# breadboard-small.net
KiCad netlist of a schematic drawn in EAGLE
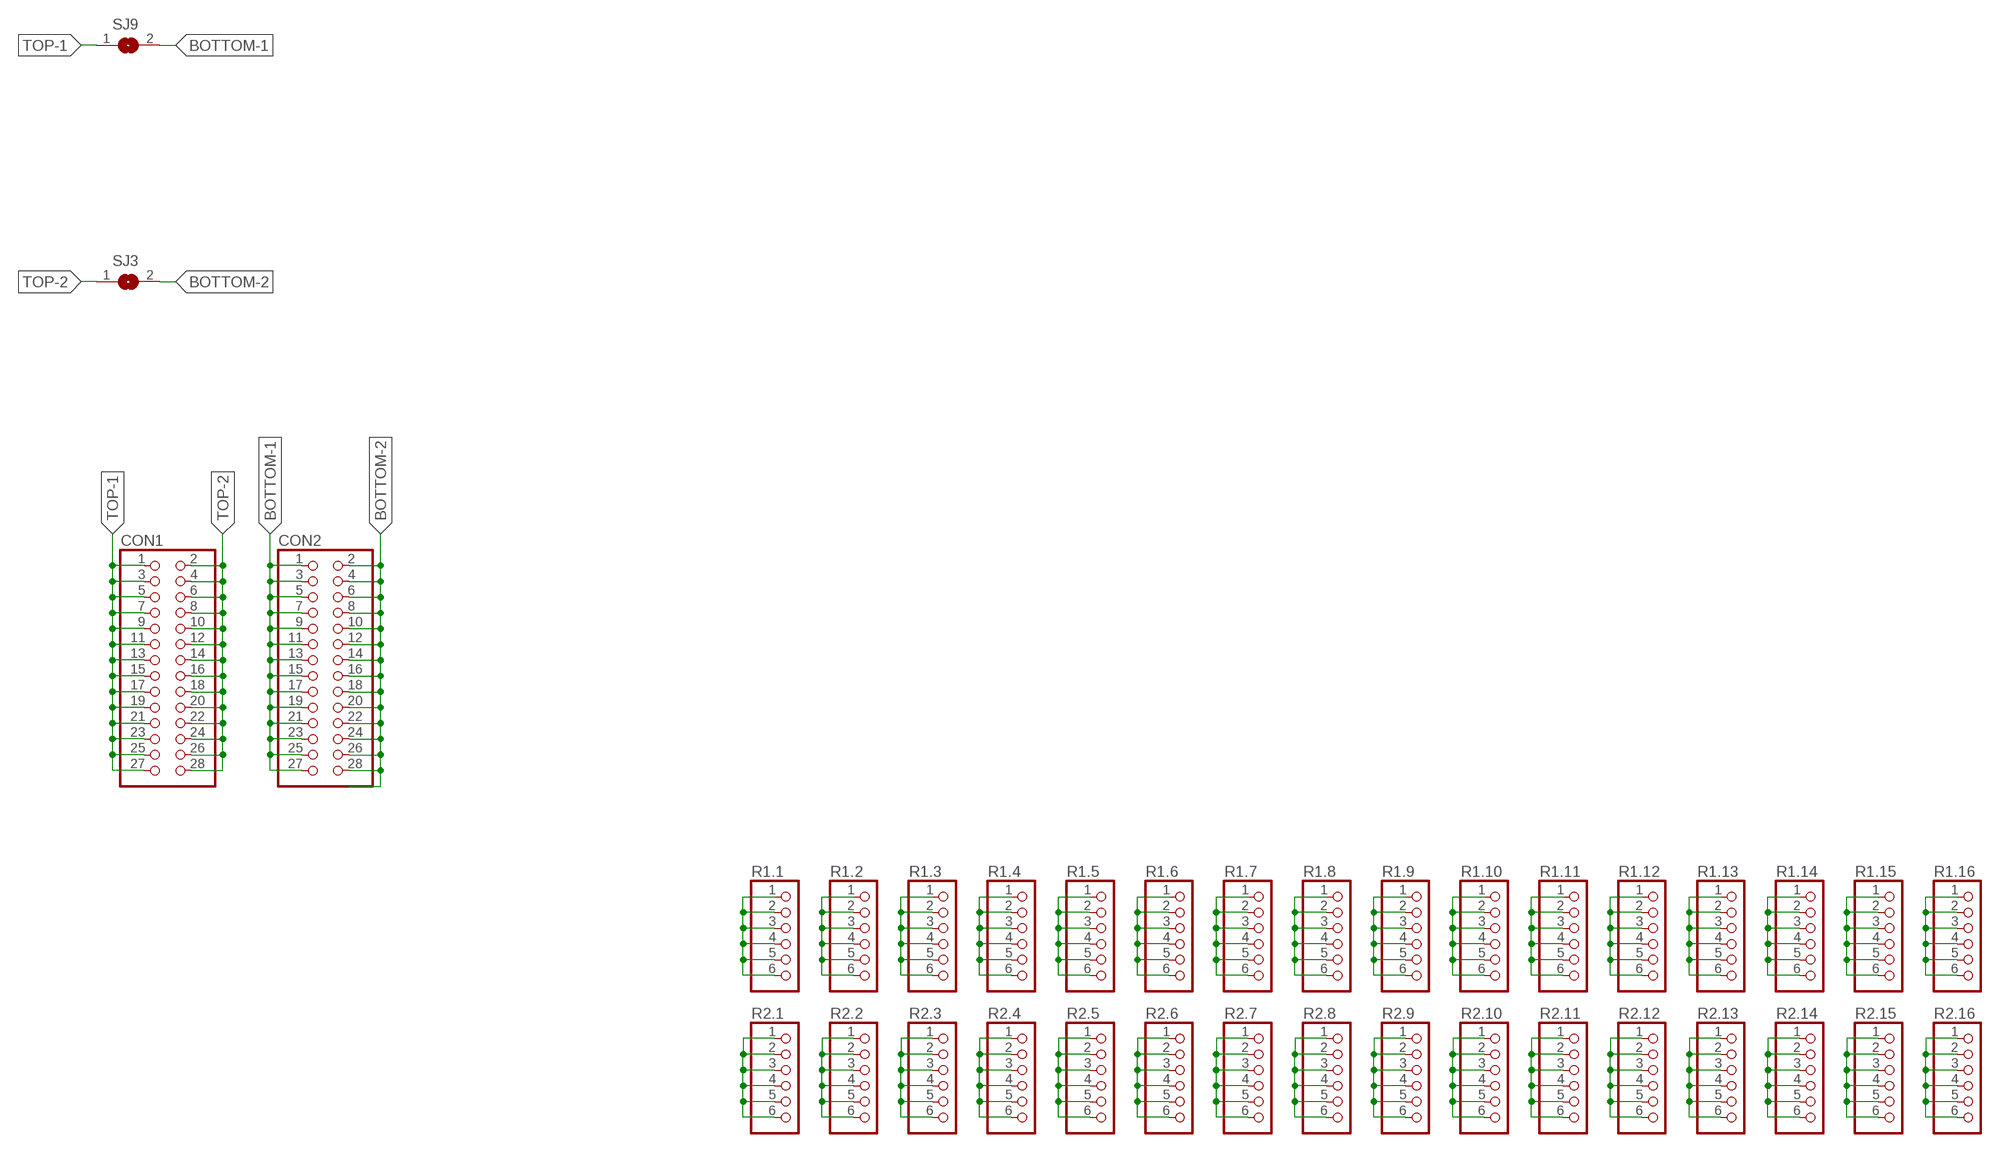
[diagram p0: schematic, sheet 1]

(export (version "E")
  (design (tool "Eeschema 10.0.6"))
  (components
    (comp (ref "CON1")
      (value "GENERIC-2X14")
      (footprint "eagle-import:PINHEADER-100MIL-2X14-NOSILK")
      (libsource (lib "eagle-import") (part "GENERIC-2X14"))
    )
    (comp (ref "CON2")
      (value "GENERIC-2X14")
      (footprint "eagle-import:PINHEADER-100MIL-2X14-NOSILK")
      (libsource (lib "eagle-import") (part "GENERIC-2X14"))
    )
    (comp (ref "R1.1")
      (value "GENERIC-1X6")
      (footprint "eagle-import:PINHEADER-100MIL-1X6-NOSILK")
      (libsource (lib "eagle-import") (part "GENERIC-1X6"))
    )
    (comp (ref "R1.2")
      (value "GENERIC-1X6")
      (footprint "eagle-import:PINHEADER-100MIL-1X6-NOSILK")
      (libsource (lib "eagle-import") (part "GENERIC-1X6"))
    )
    (comp (ref "R1.3")
      (value "GENERIC-1X6")
      (footprint "eagle-import:PINHEADER-100MIL-1X6-NOSILK")
      (libsource (lib "eagle-import") (part "GENERIC-1X6"))
    )
    (comp (ref "R1.4")
      (value "GENERIC-1X6")
      (footprint "eagle-import:PINHEADER-100MIL-1X6-NOSILK")
      (libsource (lib "eagle-import") (part "GENERIC-1X6"))
    )
    (comp (ref "R1.5")
      (value "GENERIC-1X6")
      (footprint "eagle-import:PINHEADER-100MIL-1X6-NOSILK")
      (libsource (lib "eagle-import") (part "GENERIC-1X6"))
    )
    (comp (ref "R1.6")
      (value "GENERIC-1X6")
      (footprint "eagle-import:PINHEADER-100MIL-1X6-NOSILK")
      (libsource (lib "eagle-import") (part "GENERIC-1X6"))
    )
    (comp (ref "R1.7")
      (value "GENERIC-1X6")
      (footprint "eagle-import:PINHEADER-100MIL-1X6-NOSILK")
      (libsource (lib "eagle-import") (part "GENERIC-1X6"))
    )
    (comp (ref "R1.8")
      (value "GENERIC-1X6")
      (footprint "eagle-import:PINHEADER-100MIL-1X6-NOSILK")
      (libsource (lib "eagle-import") (part "GENERIC-1X6"))
    )
    (comp (ref "R1.9")
      (value "GENERIC-1X6")
      (footprint "eagle-import:PINHEADER-100MIL-1X6-NOSILK")
      (libsource (lib "eagle-import") (part "GENERIC-1X6"))
    )
    (comp (ref "R1.10")
      (value "GENERIC-1X6")
      (footprint "eagle-import:PINHEADER-100MIL-1X6-NOSILK")
      (libsource (lib "eagle-import") (part "GENERIC-1X6"))
    )
    (comp (ref "R1.11")
      (value "GENERIC-1X6")
      (footprint "eagle-import:PINHEADER-100MIL-1X6-NOSILK")
      (libsource (lib "eagle-import") (part "GENERIC-1X6"))
    )
    (comp (ref "R1.12")
      (value "GENERIC-1X6")
      (footprint "eagle-import:PINHEADER-100MIL-1X6-NOSILK")
      (libsource (lib "eagle-import") (part "GENERIC-1X6"))
    )
    (comp (ref "R1.13")
      (value "GENERIC-1X6")
      (footprint "eagle-import:PINHEADER-100MIL-1X6-NOSILK")
      (libsource (lib "eagle-import") (part "GENERIC-1X6"))
    )
    (comp (ref "R1.14")
      (value "GENERIC-1X6")
      (footprint "eagle-import:PINHEADER-100MIL-1X6-NOSILK")
      (libsource (lib "eagle-import") (part "GENERIC-1X6"))
    )
    (comp (ref "R1.15")
      (value "GENERIC-1X6")
      (footprint "eagle-import:PINHEADER-100MIL-1X6-NOSILK")
      (libsource (lib "eagle-import") (part "GENERIC-1X6"))
    )
    (comp (ref "R1.16")
      (value "GENERIC-1X6")
      (footprint "eagle-import:PINHEADER-100MIL-1X6-NOSILK")
      (libsource (lib "eagle-import") (part "GENERIC-1X6"))
    )
    (comp (ref "R2.1")
      (value "GENERIC-1X6")
      (footprint "eagle-import:PINHEADER-100MIL-1X6-NOSILK")
      (libsource (lib "eagle-import") (part "GENERIC-1X6"))
    )
    (comp (ref "R2.2")
      (value "GENERIC-1X6")
      (footprint "eagle-import:PINHEADER-100MIL-1X6-NOSILK")
      (libsource (lib "eagle-import") (part "GENERIC-1X6"))
    )
    (comp (ref "R2.3")
      (value "GENERIC-1X6")
      (footprint "eagle-import:PINHEADER-100MIL-1X6-NOSILK")
      (libsource (lib "eagle-import") (part "GENERIC-1X6"))
    )
    (comp (ref "R2.4")
      (value "GENERIC-1X6")
      (footprint "eagle-import:PINHEADER-100MIL-1X6-NOSILK")
      (libsource (lib "eagle-import") (part "GENERIC-1X6"))
    )
    (comp (ref "R2.5")
      (value "GENERIC-1X6")
      (footprint "eagle-import:PINHEADER-100MIL-1X6-NOSILK")
      (libsource (lib "eagle-import") (part "GENERIC-1X6"))
    )
    (comp (ref "R2.6")
      (value "GENERIC-1X6")
      (footprint "eagle-import:PINHEADER-100MIL-1X6-NOSILK")
      (libsource (lib "eagle-import") (part "GENERIC-1X6"))
    )
    (comp (ref "R2.7")
      (value "GENERIC-1X6")
      (footprint "eagle-import:PINHEADER-100MIL-1X6-NOSILK")
      (libsource (lib "eagle-import") (part "GENERIC-1X6"))
    )
    (comp (ref "R2.8")
      (value "GENERIC-1X6")
      (footprint "eagle-import:PINHEADER-100MIL-1X6-NOSILK")
      (libsource (lib "eagle-import") (part "GENERIC-1X6"))
    )
    (comp (ref "R2.9")
      (value "GENERIC-1X6")
      (footprint "eagle-import:PINHEADER-100MIL-1X6-NOSILK")
      (libsource (lib "eagle-import") (part "GENERIC-1X6"))
    )
    (comp (ref "R2.10")
      (value "GENERIC-1X6")
      (footprint "eagle-import:PINHEADER-100MIL-1X6-NOSILK")
      (libsource (lib "eagle-import") (part "GENERIC-1X6"))
    )
    (comp (ref "R2.11")
      (value "GENERIC-1X6")
      (footprint "eagle-import:PINHEADER-100MIL-1X6-NOSILK")
      (libsource (lib "eagle-import") (part "GENERIC-1X6"))
    )
    (comp (ref "R2.12")
      (value "GENERIC-1X6")
      (footprint "eagle-import:PINHEADER-100MIL-1X6-NOSILK")
      (libsource (lib "eagle-import") (part "GENERIC-1X6"))
    )
    (comp (ref "R2.13")
      (value "GENERIC-1X6")
      (footprint "eagle-import:PINHEADER-100MIL-1X6-NOSILK")
      (libsource (lib "eagle-import") (part "GENERIC-1X6"))
    )
    (comp (ref "R2.14")
      (value "GENERIC-1X6")
      (footprint "eagle-import:PINHEADER-100MIL-1X6-NOSILK")
      (libsource (lib "eagle-import") (part "GENERIC-1X6"))
    )
    (comp (ref "R2.15")
      (value "GENERIC-1X6")
      (footprint "eagle-import:PINHEADER-100MIL-1X6-NOSILK")
      (libsource (lib "eagle-import") (part "GENERIC-1X6"))
    )
    (comp (ref "R2.16")
      (value "GENERIC-1X6")
      (footprint "eagle-import:PINHEADER-100MIL-1X6-NOSILK")
      (libsource (lib "eagle-import") (part "GENERIC-1X6"))
    )
    (comp (ref "SJ3") (value "SJ") (footprint "eagle-import:SJ") (libsource (lib "eagle-import") (part "SJ")))
    (comp (ref "SJ9") (value "SJ") (footprint "eagle-import:SJ") (libsource (lib "eagle-import") (part "SJ")))
  )
  (nets
    (net (code "1") (name "BOTTOM-1") (class "Default")
      (node (ref "CON2") (pin "1") (pinfunction "1_1") (pintype "passive"))
      (node (ref "CON2") (pin "11") (pinfunction "11_11") (pintype "passive"))
      (node (ref "CON2") (pin "13") (pinfunction "13_13") (pintype "passive"))
      (node (ref "CON2") (pin "15") (pinfunction "15_15") (pintype "passive"))
      (node (ref "CON2") (pin "17") (pinfunction "17_17") (pintype "passive"))
      (node (ref "CON2") (pin "19") (pinfunction "19_19") (pintype "passive"))
      (node (ref "CON2") (pin "21") (pinfunction "21_21") (pintype "passive"))
      (node (ref "CON2") (pin "23") (pinfunction "23_23") (pintype "passive"))
      (node (ref "CON2") (pin "25") (pinfunction "25_25") (pintype "passive"))
      (node (ref "CON2") (pin "27") (pinfunction "27_27") (pintype "passive"))
      (node (ref "CON2") (pin "3") (pinfunction "3_3") (pintype "passive"))
      (node (ref "CON2") (pin "5") (pinfunction "5_5") (pintype "passive"))
      (node (ref "CON2") (pin "7") (pinfunction "7_7") (pintype "passive"))
      (node (ref "CON2") (pin "9") (pinfunction "9_9") (pintype "passive"))
      (node (ref "SJ9") (pin "2") (pinfunction "2_2") (pintype "passive"))
    )
    (net (code "2") (name "BOTTOM-2") (class "Default")
      (node (ref "CON2") (pin "10") (pinfunction "10_10") (pintype "passive"))
      (node (ref "CON2") (pin "12") (pinfunction "12_12") (pintype "passive"))
      (node (ref "CON2") (pin "14") (pinfunction "14_14") (pintype "passive"))
      (node (ref "CON2") (pin "16") (pinfunction "16_16") (pintype "passive"))
      (node (ref "CON2") (pin "18") (pinfunction "18_18") (pintype "passive"))
      (node (ref "CON2") (pin "2") (pinfunction "2_2") (pintype "passive"))
      (node (ref "CON2") (pin "20") (pinfunction "20_20") (pintype "passive"))
      (node (ref "CON2") (pin "22") (pinfunction "22_22") (pintype "passive"))
      (node (ref "CON2") (pin "24") (pinfunction "24_24") (pintype "passive"))
      (node (ref "CON2") (pin "26") (pinfunction "26_26") (pintype "passive"))
      (node (ref "CON2") (pin "28") (pinfunction "28_28") (pintype "passive"))
      (node (ref "CON2") (pin "4") (pinfunction "4_4") (pintype "passive"))
      (node (ref "CON2") (pin "6") (pinfunction "6_6") (pintype "passive"))
      (node (ref "CON2") (pin "8") (pinfunction "8_8") (pintype "passive"))
      (node (ref "SJ3") (pin "2") (pinfunction "2_2") (pintype "passive"))
    )
    (net (code "3") (name "Net-(R1.1-Pad1)") (class "Default")
      (node (ref "R1.1") (pin "1") (pinfunction "1_1") (pintype "passive"))
      (node (ref "R1.1") (pin "2") (pinfunction "2_2") (pintype "passive"))
      (node (ref "R1.1") (pin "3") (pinfunction "3_3") (pintype "passive"))
      (node (ref "R1.1") (pin "4") (pinfunction "4_4") (pintype "passive"))
      (node (ref "R1.1") (pin "5") (pinfunction "5_5") (pintype "passive"))
      (node (ref "R1.1") (pin "6") (pinfunction "6_6") (pintype "passive"))
    )
    (net (code "4") (name "Net-(R1.2-Pad1)") (class "Default")
      (node (ref "R1.2") (pin "1") (pinfunction "1_1") (pintype "passive"))
      (node (ref "R1.2") (pin "2") (pinfunction "2_2") (pintype "passive"))
      (node (ref "R1.2") (pin "3") (pinfunction "3_3") (pintype "passive"))
      (node (ref "R1.2") (pin "4") (pinfunction "4_4") (pintype "passive"))
      (node (ref "R1.2") (pin "5") (pinfunction "5_5") (pintype "passive"))
      (node (ref "R1.2") (pin "6") (pinfunction "6_6") (pintype "passive"))
    )
    (net (code "5") (name "Net-(R1.3-Pad1)") (class "Default")
      (node (ref "R1.3") (pin "1") (pinfunction "1_1") (pintype "passive"))
      (node (ref "R1.3") (pin "2") (pinfunction "2_2") (pintype "passive"))
      (node (ref "R1.3") (pin "3") (pinfunction "3_3") (pintype "passive"))
      (node (ref "R1.3") (pin "4") (pinfunction "4_4") (pintype "passive"))
      (node (ref "R1.3") (pin "5") (pinfunction "5_5") (pintype "passive"))
      (node (ref "R1.3") (pin "6") (pinfunction "6_6") (pintype "passive"))
    )
    (net (code "6") (name "Net-(R1.4-Pad1)") (class "Default")
      (node (ref "R1.4") (pin "1") (pinfunction "1_1") (pintype "passive"))
      (node (ref "R1.4") (pin "2") (pinfunction "2_2") (pintype "passive"))
      (node (ref "R1.4") (pin "3") (pinfunction "3_3") (pintype "passive"))
      (node (ref "R1.4") (pin "4") (pinfunction "4_4") (pintype "passive"))
      (node (ref "R1.4") (pin "5") (pinfunction "5_5") (pintype "passive"))
      (node (ref "R1.4") (pin "6") (pinfunction "6_6") (pintype "passive"))
    )
    (net (code "7") (name "Net-(R1.5-Pad1)") (class "Default")
      (node (ref "R1.5") (pin "1") (pinfunction "1_1") (pintype "passive"))
      (node (ref "R1.5") (pin "2") (pinfunction "2_2") (pintype "passive"))
      (node (ref "R1.5") (pin "3") (pinfunction "3_3") (pintype "passive"))
      (node (ref "R1.5") (pin "4") (pinfunction "4_4") (pintype "passive"))
      (node (ref "R1.5") (pin "5") (pinfunction "5_5") (pintype "passive"))
      (node (ref "R1.5") (pin "6") (pinfunction "6_6") (pintype "passive"))
    )
    (net (code "8") (name "Net-(R1.6-Pad1)") (class "Default")
      (node (ref "R1.6") (pin "1") (pinfunction "1_1") (pintype "passive"))
      (node (ref "R1.6") (pin "2") (pinfunction "2_2") (pintype "passive"))
      (node (ref "R1.6") (pin "3") (pinfunction "3_3") (pintype "passive"))
      (node (ref "R1.6") (pin "4") (pinfunction "4_4") (pintype "passive"))
      (node (ref "R1.6") (pin "5") (pinfunction "5_5") (pintype "passive"))
      (node (ref "R1.6") (pin "6") (pinfunction "6_6") (pintype "passive"))
    )
    (net (code "9") (name "Net-(R1.7-Pad1)") (class "Default")
      (node (ref "R1.7") (pin "1") (pinfunction "1_1") (pintype "passive"))
      (node (ref "R1.7") (pin "2") (pinfunction "2_2") (pintype "passive"))
      (node (ref "R1.7") (pin "3") (pinfunction "3_3") (pintype "passive"))
      (node (ref "R1.7") (pin "4") (pinfunction "4_4") (pintype "passive"))
      (node (ref "R1.7") (pin "5") (pinfunction "5_5") (pintype "passive"))
      (node (ref "R1.7") (pin "6") (pinfunction "6_6") (pintype "passive"))
    )
    (net (code "10") (name "Net-(R1.8-Pad1)") (class "Default")
      (node (ref "R1.8") (pin "1") (pinfunction "1_1") (pintype "passive"))
      (node (ref "R1.8") (pin "2") (pinfunction "2_2") (pintype "passive"))
      (node (ref "R1.8") (pin "3") (pinfunction "3_3") (pintype "passive"))
      (node (ref "R1.8") (pin "4") (pinfunction "4_4") (pintype "passive"))
      (node (ref "R1.8") (pin "5") (pinfunction "5_5") (pintype "passive"))
      (node (ref "R1.8") (pin "6") (pinfunction "6_6") (pintype "passive"))
    )
    (net (code "11") (name "Net-(R1.9-Pad1)") (class "Default")
      (node (ref "R1.9") (pin "1") (pinfunction "1_1") (pintype "passive"))
      (node (ref "R1.9") (pin "2") (pinfunction "2_2") (pintype "passive"))
      (node (ref "R1.9") (pin "3") (pinfunction "3_3") (pintype "passive"))
      (node (ref "R1.9") (pin "4") (pinfunction "4_4") (pintype "passive"))
      (node (ref "R1.9") (pin "5") (pinfunction "5_5") (pintype "passive"))
      (node (ref "R1.9") (pin "6") (pinfunction "6_6") (pintype "passive"))
    )
    (net (code "12") (name "Net-(R1.10-Pad1)") (class "Default")
      (node (ref "R1.10") (pin "1") (pinfunction "1_1") (pintype "passive"))
      (node (ref "R1.10") (pin "2") (pinfunction "2_2") (pintype "passive"))
      (node (ref "R1.10") (pin "3") (pinfunction "3_3") (pintype "passive"))
      (node (ref "R1.10") (pin "4") (pinfunction "4_4") (pintype "passive"))
      (node (ref "R1.10") (pin "5") (pinfunction "5_5") (pintype "passive"))
      (node (ref "R1.10") (pin "6") (pinfunction "6_6") (pintype "passive"))
    )
    (net (code "13") (name "Net-(R1.11-Pad1)") (class "Default")
      (node (ref "R1.11") (pin "1") (pinfunction "1_1") (pintype "passive"))
      (node (ref "R1.11") (pin "2") (pinfunction "2_2") (pintype "passive"))
      (node (ref "R1.11") (pin "3") (pinfunction "3_3") (pintype "passive"))
      (node (ref "R1.11") (pin "4") (pinfunction "4_4") (pintype "passive"))
      (node (ref "R1.11") (pin "5") (pinfunction "5_5") (pintype "passive"))
      (node (ref "R1.11") (pin "6") (pinfunction "6_6") (pintype "passive"))
    )
    (net (code "14") (name "Net-(R1.12-Pad1)") (class "Default")
      (node (ref "R1.12") (pin "1") (pinfunction "1_1") (pintype "passive"))
      (node (ref "R1.12") (pin "2") (pinfunction "2_2") (pintype "passive"))
      (node (ref "R1.12") (pin "3") (pinfunction "3_3") (pintype "passive"))
      (node (ref "R1.12") (pin "4") (pinfunction "4_4") (pintype "passive"))
      (node (ref "R1.12") (pin "5") (pinfunction "5_5") (pintype "passive"))
      (node (ref "R1.12") (pin "6") (pinfunction "6_6") (pintype "passive"))
    )
    (net (code "15") (name "Net-(R1.13-Pad1)") (class "Default")
      (node (ref "R1.13") (pin "1") (pinfunction "1_1") (pintype "passive"))
      (node (ref "R1.13") (pin "2") (pinfunction "2_2") (pintype "passive"))
      (node (ref "R1.13") (pin "3") (pinfunction "3_3") (pintype "passive"))
      (node (ref "R1.13") (pin "4") (pinfunction "4_4") (pintype "passive"))
      (node (ref "R1.13") (pin "5") (pinfunction "5_5") (pintype "passive"))
      (node (ref "R1.13") (pin "6") (pinfunction "6_6") (pintype "passive"))
    )
    (net (code "16") (name "Net-(R1.14-Pad1)") (class "Default")
      (node (ref "R1.14") (pin "1") (pinfunction "1_1") (pintype "passive"))
      (node (ref "R1.14") (pin "2") (pinfunction "2_2") (pintype "passive"))
      (node (ref "R1.14") (pin "3") (pinfunction "3_3") (pintype "passive"))
      (node (ref "R1.14") (pin "4") (pinfunction "4_4") (pintype "passive"))
      (node (ref "R1.14") (pin "5") (pinfunction "5_5") (pintype "passive"))
      (node (ref "R1.14") (pin "6") (pinfunction "6_6") (pintype "passive"))
    )
    (net (code "17") (name "Net-(R1.15-Pad1)") (class "Default")
      (node (ref "R1.15") (pin "1") (pinfunction "1_1") (pintype "passive"))
      (node (ref "R1.15") (pin "2") (pinfunction "2_2") (pintype "passive"))
      (node (ref "R1.15") (pin "3") (pinfunction "3_3") (pintype "passive"))
      (node (ref "R1.15") (pin "4") (pinfunction "4_4") (pintype "passive"))
      (node (ref "R1.15") (pin "5") (pinfunction "5_5") (pintype "passive"))
      (node (ref "R1.15") (pin "6") (pinfunction "6_6") (pintype "passive"))
    )
    (net (code "18") (name "Net-(R1.16-Pad1)") (class "Default")
      (node (ref "R1.16") (pin "1") (pinfunction "1_1") (pintype "passive"))
      (node (ref "R1.16") (pin "2") (pinfunction "2_2") (pintype "passive"))
      (node (ref "R1.16") (pin "3") (pinfunction "3_3") (pintype "passive"))
      (node (ref "R1.16") (pin "4") (pinfunction "4_4") (pintype "passive"))
      (node (ref "R1.16") (pin "5") (pinfunction "5_5") (pintype "passive"))
      (node (ref "R1.16") (pin "6") (pinfunction "6_6") (pintype "passive"))
    )
    (net (code "19") (name "Net-(R2.1-Pad1)") (class "Default")
      (node (ref "R2.1") (pin "1") (pinfunction "1_1") (pintype "passive"))
      (node (ref "R2.1") (pin "2") (pinfunction "2_2") (pintype "passive"))
      (node (ref "R2.1") (pin "3") (pinfunction "3_3") (pintype "passive"))
      (node (ref "R2.1") (pin "4") (pinfunction "4_4") (pintype "passive"))
      (node (ref "R2.1") (pin "5") (pinfunction "5_5") (pintype "passive"))
      (node (ref "R2.1") (pin "6") (pinfunction "6_6") (pintype "passive"))
    )
    (net (code "20") (name "Net-(R2.2-Pad1)") (class "Default")
      (node (ref "R2.2") (pin "1") (pinfunction "1_1") (pintype "passive"))
      (node (ref "R2.2") (pin "2") (pinfunction "2_2") (pintype "passive"))
      (node (ref "R2.2") (pin "3") (pinfunction "3_3") (pintype "passive"))
      (node (ref "R2.2") (pin "4") (pinfunction "4_4") (pintype "passive"))
      (node (ref "R2.2") (pin "5") (pinfunction "5_5") (pintype "passive"))
      (node (ref "R2.2") (pin "6") (pinfunction "6_6") (pintype "passive"))
    )
    (net (code "21") (name "Net-(R2.3-Pad1)") (class "Default")
      (node (ref "R2.3") (pin "1") (pinfunction "1_1") (pintype "passive"))
      (node (ref "R2.3") (pin "2") (pinfunction "2_2") (pintype "passive"))
      (node (ref "R2.3") (pin "3") (pinfunction "3_3") (pintype "passive"))
      (node (ref "R2.3") (pin "4") (pinfunction "4_4") (pintype "passive"))
      (node (ref "R2.3") (pin "5") (pinfunction "5_5") (pintype "passive"))
      (node (ref "R2.3") (pin "6") (pinfunction "6_6") (pintype "passive"))
    )
    (net (code "22") (name "Net-(R2.4-Pad1)") (class "Default")
      (node (ref "R2.4") (pin "1") (pinfunction "1_1") (pintype "passive"))
      (node (ref "R2.4") (pin "2") (pinfunction "2_2") (pintype "passive"))
      (node (ref "R2.4") (pin "3") (pinfunction "3_3") (pintype "passive"))
      (node (ref "R2.4") (pin "4") (pinfunction "4_4") (pintype "passive"))
      (node (ref "R2.4") (pin "5") (pinfunction "5_5") (pintype "passive"))
      (node (ref "R2.4") (pin "6") (pinfunction "6_6") (pintype "passive"))
    )
    (net (code "23") (name "Net-(R2.5-Pad1)") (class "Default")
      (node (ref "R2.5") (pin "1") (pinfunction "1_1") (pintype "passive"))
      (node (ref "R2.5") (pin "2") (pinfunction "2_2") (pintype "passive"))
      (node (ref "R2.5") (pin "3") (pinfunction "3_3") (pintype "passive"))
      (node (ref "R2.5") (pin "4") (pinfunction "4_4") (pintype "passive"))
      (node (ref "R2.5") (pin "5") (pinfunction "5_5") (pintype "passive"))
      (node (ref "R2.5") (pin "6") (pinfunction "6_6") (pintype "passive"))
    )
    (net (code "24") (name "Net-(R2.6-Pad1)") (class "Default")
      (node (ref "R2.6") (pin "1") (pinfunction "1_1") (pintype "passive"))
      (node (ref "R2.6") (pin "2") (pinfunction "2_2") (pintype "passive"))
      (node (ref "R2.6") (pin "3") (pinfunction "3_3") (pintype "passive"))
      (node (ref "R2.6") (pin "4") (pinfunction "4_4") (pintype "passive"))
      (node (ref "R2.6") (pin "5") (pinfunction "5_5") (pintype "passive"))
      (node (ref "R2.6") (pin "6") (pinfunction "6_6") (pintype "passive"))
    )
    (net (code "25") (name "Net-(R2.7-Pad1)") (class "Default")
      (node (ref "R2.7") (pin "1") (pinfunction "1_1") (pintype "passive"))
      (node (ref "R2.7") (pin "2") (pinfunction "2_2") (pintype "passive"))
      (node (ref "R2.7") (pin "3") (pinfunction "3_3") (pintype "passive"))
      (node (ref "R2.7") (pin "4") (pinfunction "4_4") (pintype "passive"))
      (node (ref "R2.7") (pin "5") (pinfunction "5_5") (pintype "passive"))
      (node (ref "R2.7") (pin "6") (pinfunction "6_6") (pintype "passive"))
    )
    (net (code "26") (name "Net-(R2.8-Pad1)") (class "Default")
      (node (ref "R2.8") (pin "1") (pinfunction "1_1") (pintype "passive"))
      (node (ref "R2.8") (pin "2") (pinfunction "2_2") (pintype "passive"))
      (node (ref "R2.8") (pin "3") (pinfunction "3_3") (pintype "passive"))
      (node (ref "R2.8") (pin "4") (pinfunction "4_4") (pintype "passive"))
      (node (ref "R2.8") (pin "5") (pinfunction "5_5") (pintype "passive"))
      (node (ref "R2.8") (pin "6") (pinfunction "6_6") (pintype "passive"))
    )
    (net (code "27") (name "Net-(R2.9-Pad1)") (class "Default")
      (node (ref "R2.9") (pin "1") (pinfunction "1_1") (pintype "passive"))
      (node (ref "R2.9") (pin "2") (pinfunction "2_2") (pintype "passive"))
      (node (ref "R2.9") (pin "3") (pinfunction "3_3") (pintype "passive"))
      (node (ref "R2.9") (pin "4") (pinfunction "4_4") (pintype "passive"))
      (node (ref "R2.9") (pin "5") (pinfunction "5_5") (pintype "passive"))
      (node (ref "R2.9") (pin "6") (pinfunction "6_6") (pintype "passive"))
    )
    (net (code "28") (name "Net-(R2.10-Pad1)") (class "Default")
      (node (ref "R2.10") (pin "1") (pinfunction "1_1") (pintype "passive"))
      (node (ref "R2.10") (pin "2") (pinfunction "2_2") (pintype "passive"))
      (node (ref "R2.10") (pin "3") (pinfunction "3_3") (pintype "passive"))
      (node (ref "R2.10") (pin "4") (pinfunction "4_4") (pintype "passive"))
      (node (ref "R2.10") (pin "5") (pinfunction "5_5") (pintype "passive"))
      (node (ref "R2.10") (pin "6") (pinfunction "6_6") (pintype "passive"))
    )
    (net (code "29") (name "Net-(R2.11-Pad1)") (class "Default")
      (node (ref "R2.11") (pin "1") (pinfunction "1_1") (pintype "passive"))
      (node (ref "R2.11") (pin "2") (pinfunction "2_2") (pintype "passive"))
      (node (ref "R2.11") (pin "3") (pinfunction "3_3") (pintype "passive"))
      (node (ref "R2.11") (pin "4") (pinfunction "4_4") (pintype "passive"))
      (node (ref "R2.11") (pin "5") (pinfunction "5_5") (pintype "passive"))
      (node (ref "R2.11") (pin "6") (pinfunction "6_6") (pintype "passive"))
    )
    (net (code "30") (name "Net-(R2.12-Pad1)") (class "Default")
      (node (ref "R2.12") (pin "1") (pinfunction "1_1") (pintype "passive"))
      (node (ref "R2.12") (pin "2") (pinfunction "2_2") (pintype "passive"))
      (node (ref "R2.12") (pin "3") (pinfunction "3_3") (pintype "passive"))
      (node (ref "R2.12") (pin "4") (pinfunction "4_4") (pintype "passive"))
      (node (ref "R2.12") (pin "5") (pinfunction "5_5") (pintype "passive"))
      (node (ref "R2.12") (pin "6") (pinfunction "6_6") (pintype "passive"))
    )
    (net (code "31") (name "Net-(R2.13-Pad1)") (class "Default")
      (node (ref "R2.13") (pin "1") (pinfunction "1_1") (pintype "passive"))
      (node (ref "R2.13") (pin "2") (pinfunction "2_2") (pintype "passive"))
      (node (ref "R2.13") (pin "3") (pinfunction "3_3") (pintype "passive"))
      (node (ref "R2.13") (pin "4") (pinfunction "4_4") (pintype "passive"))
      (node (ref "R2.13") (pin "5") (pinfunction "5_5") (pintype "passive"))
      (node (ref "R2.13") (pin "6") (pinfunction "6_6") (pintype "passive"))
    )
    (net (code "32") (name "Net-(R2.14-Pad1)") (class "Default")
      (node (ref "R2.14") (pin "1") (pinfunction "1_1") (pintype "passive"))
      (node (ref "R2.14") (pin "2") (pinfunction "2_2") (pintype "passive"))
      (node (ref "R2.14") (pin "3") (pinfunction "3_3") (pintype "passive"))
      (node (ref "R2.14") (pin "4") (pinfunction "4_4") (pintype "passive"))
      (node (ref "R2.14") (pin "5") (pinfunction "5_5") (pintype "passive"))
      (node (ref "R2.14") (pin "6") (pinfunction "6_6") (pintype "passive"))
    )
    (net (code "33") (name "Net-(R2.15-Pad1)") (class "Default")
      (node (ref "R2.15") (pin "1") (pinfunction "1_1") (pintype "passive"))
      (node (ref "R2.15") (pin "2") (pinfunction "2_2") (pintype "passive"))
      (node (ref "R2.15") (pin "3") (pinfunction "3_3") (pintype "passive"))
      (node (ref "R2.15") (pin "4") (pinfunction "4_4") (pintype "passive"))
      (node (ref "R2.15") (pin "5") (pinfunction "5_5") (pintype "passive"))
      (node (ref "R2.15") (pin "6") (pinfunction "6_6") (pintype "passive"))
    )
    (net (code "34") (name "Net-(R2.16-Pad1)") (class "Default")
      (node (ref "R2.16") (pin "1") (pinfunction "1_1") (pintype "passive"))
      (node (ref "R2.16") (pin "2") (pinfunction "2_2") (pintype "passive"))
      (node (ref "R2.16") (pin "3") (pinfunction "3_3") (pintype "passive"))
      (node (ref "R2.16") (pin "4") (pinfunction "4_4") (pintype "passive"))
      (node (ref "R2.16") (pin "5") (pinfunction "5_5") (pintype "passive"))
      (node (ref "R2.16") (pin "6") (pinfunction "6_6") (pintype "passive"))
    )
    (net (code "35") (name "TOP-1") (class "Default")
      (node (ref "CON1") (pin "1") (pinfunction "1_1") (pintype "passive"))
      (node (ref "CON1") (pin "11") (pinfunction "11_11") (pintype "passive"))
      (node (ref "CON1") (pin "13") (pinfunction "13_13") (pintype "passive"))
      (node (ref "CON1") (pin "15") (pinfunction "15_15") (pintype "passive"))
      (node (ref "CON1") (pin "17") (pinfunction "17_17") (pintype "passive"))
      (node (ref "CON1") (pin "19") (pinfunction "19_19") (pintype "passive"))
      (node (ref "CON1") (pin "21") (pinfunction "21_21") (pintype "passive"))
      (node (ref "CON1") (pin "23") (pinfunction "23_23") (pintype "passive"))
      (node (ref "CON1") (pin "25") (pinfunction "25_25") (pintype "passive"))
      (node (ref "CON1") (pin "27") (pinfunction "27_27") (pintype "passive"))
      (node (ref "CON1") (pin "3") (pinfunction "3_3") (pintype "passive"))
      (node (ref "CON1") (pin "5") (pinfunction "5_5") (pintype "passive"))
      (node (ref "CON1") (pin "7") (pinfunction "7_7") (pintype "passive"))
      (node (ref "CON1") (pin "9") (pinfunction "9_9") (pintype "passive"))
      (node (ref "SJ9") (pin "1") (pinfunction "1_1") (pintype "passive"))
    )
    (net (code "36") (name "TOP-2") (class "Default")
      (node (ref "CON1") (pin "10") (pinfunction "10_10") (pintype "passive"))
      (node (ref "CON1") (pin "12") (pinfunction "12_12") (pintype "passive"))
      (node (ref "CON1") (pin "14") (pinfunction "14_14") (pintype "passive"))
      (node (ref "CON1") (pin "16") (pinfunction "16_16") (pintype "passive"))
      (node (ref "CON1") (pin "18") (pinfunction "18_18") (pintype "passive"))
      (node (ref "CON1") (pin "2") (pinfunction "2_2") (pintype "passive"))
      (node (ref "CON1") (pin "20") (pinfunction "20_20") (pintype "passive"))
      (node (ref "CON1") (pin "22") (pinfunction "22_22") (pintype "passive"))
      (node (ref "CON1") (pin "24") (pinfunction "24_24") (pintype "passive"))
      (node (ref "CON1") (pin "26") (pinfunction "26_26") (pintype "passive"))
      (node (ref "CON1") (pin "28") (pinfunction "28_28") (pintype "passive"))
      (node (ref "CON1") (pin "4") (pinfunction "4_4") (pintype "passive"))
      (node (ref "CON1") (pin "6") (pinfunction "6_6") (pintype "passive"))
      (node (ref "CON1") (pin "8") (pinfunction "8_8") (pintype "passive"))
      (node (ref "SJ3") (pin "1") (pinfunction "1_1") (pintype "passive"))
    )
  )
)
